# sevenSeg2_atmega_1A_noGND.net
KiCad netlist of a schematic drawn in EAGLE
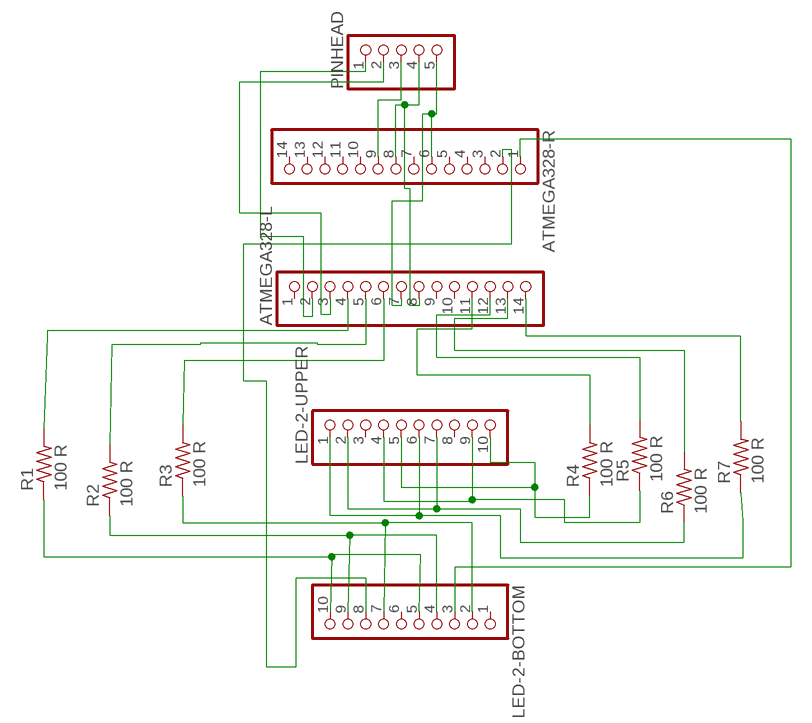
[diagram p0: schematic, sheet 1]

(export (version "E")
  (design (tool "Eeschema 10.0.6"))
  (components
    (comp (ref "ATMEGA328-L")
      (value "PINHD-1X14")
      (footprint "eagle-import:1X14")
      (libsource (lib "eagle-import") (part "PINHD-1X14"))
    )
    (comp (ref "ATMEGA328-R")
      (value "PINHD-1X14")
      (footprint "eagle-import:1X14")
      (libsource (lib "eagle-import") (part "PINHD-1X14"))
    )
    (comp (ref "LED-2-BOTTOM")
      (value "PINHD-1X10")
      (footprint "eagle-import:1X10")
      (libsource (lib "eagle-import") (part "PINHD-1X10"))
    )
    (comp (ref "LED-2-UPPER")
      (value "PINHD-1X10")
      (footprint "eagle-import:1X10")
      (libsource (lib "eagle-import") (part "PINHD-1X10"))
    )
    (comp (ref "PINHEAD")
      (value "PINHD-1X5")
      (footprint "eagle-import:1X05")
      (libsource (lib "eagle-import") (part "PINHD-1X5"))
    )
    (comp (ref "R1")
      (value "100 R")
      (footprint "eagle-import:0204_7")
      (libsource (lib "eagle-import") (part "R-US_0204/7"))
    )
    (comp (ref "R2")
      (value "100 R")
      (footprint "eagle-import:0204_7")
      (libsource (lib "eagle-import") (part "R-US_0204/7"))
    )
    (comp (ref "R3")
      (value "100 R")
      (footprint "eagle-import:0204_7")
      (libsource (lib "eagle-import") (part "R-US_0204/7"))
    )
    (comp (ref "R4")
      (value "100 R")
      (footprint "eagle-import:0204_7")
      (libsource (lib "eagle-import") (part "R-US_0204/7"))
    )
    (comp (ref "R5")
      (value "100 R")
      (footprint "eagle-import:0204_7")
      (libsource (lib "eagle-import") (part "R-US_0204/7"))
    )
    (comp (ref "R6")
      (value "100 R")
      (footprint "eagle-import:0204_7")
      (libsource (lib "eagle-import") (part "R-US_0204/7"))
    )
    (comp (ref "R7")
      (value "100 R")
      (footprint "eagle-import:0204_7")
      (libsource (lib "eagle-import") (part "R-US_0204/7"))
    )
  )
  (nets
    (net (code "1") (name "Net-(ATMEGA328-L-Pad2)") (class "Default")
      (node (ref "ATMEGA328-L") (pin "2") (pinfunction "2_2") (pintype "passive"))
      (node (ref "PINHEAD") (pin "1") (pinfunction "1_1") (pintype "passive"))
    )
    (net (code "2") (name "Net-(ATMEGA328-L-Pad3)") (class "Default")
      (node (ref "ATMEGA328-L") (pin "3") (pinfunction "3_3") (pintype "passive"))
      (node (ref "PINHEAD") (pin "2") (pinfunction "2_2") (pintype "passive"))
    )
    (net (code "3") (name "Net-(ATMEGA328-L-Pad4)") (class "Default")
      (node (ref "ATMEGA328-L") (pin "4") (pinfunction "4_4") (pintype "passive"))
      (node (ref "R1") (pin "2") (pinfunction "2_2") (pintype "passive"))
    )
    (net (code "4") (name "Net-(ATMEGA328-L-Pad5)") (class "Default")
      (node (ref "ATMEGA328-L") (pin "5") (pinfunction "5_5") (pintype "passive"))
      (node (ref "R2") (pin "2") (pinfunction "2_2") (pintype "passive"))
    )
    (net (code "5") (name "Net-(ATMEGA328-L-Pad6)") (class "Default")
      (node (ref "ATMEGA328-L") (pin "6") (pinfunction "6_6") (pintype "passive"))
      (node (ref "R3") (pin "2") (pinfunction "2_2") (pintype "passive"))
    )
    (net (code "6") (name "Net-(ATMEGA328-L-Pad7)") (class "Default")
      (node (ref "ATMEGA328-L") (pin "7") (pinfunction "7_7") (pintype "passive"))
      (node (ref "ATMEGA328-R") (pin "6") (pinfunction "6_6") (pintype "passive"))
      (node (ref "PINHEAD") (pin "5") (pinfunction "5_5") (pintype "passive"))
    )
    (net (code "7") (name "Net-(ATMEGA328-L-Pad8)") (class "Default")
      (node (ref "ATMEGA328-L") (pin "8") (pinfunction "8_8") (pintype "passive"))
      (node (ref "ATMEGA328-R") (pin "8") (pinfunction "8_8") (pintype "passive"))
      (node (ref "PINHEAD") (pin "4") (pinfunction "4_4") (pintype "passive"))
    )
    (net (code "8") (name "Net-(ATMEGA328-L-Pad11)") (class "Default")
      (node (ref "ATMEGA328-L") (pin "11") (pinfunction "11_11") (pintype "passive"))
      (node (ref "R4") (pin "2") (pinfunction "2_2") (pintype "passive"))
    )
    (net (code "9") (name "Net-(ATMEGA328-L-Pad12)") (class "Default")
      (node (ref "ATMEGA328-L") (pin "12") (pinfunction "12_12") (pintype "passive"))
      (node (ref "R5") (pin "2") (pinfunction "2_2") (pintype "passive"))
    )
    (net (code "10") (name "Net-(ATMEGA328-L-Pad13)") (class "Default")
      (node (ref "ATMEGA328-L") (pin "13") (pinfunction "13_13") (pintype "passive"))
      (node (ref "R6") (pin "2") (pinfunction "2_2") (pintype "passive"))
    )
    (net (code "11") (name "Net-(ATMEGA328-L-Pad14)") (class "Default")
      (node (ref "ATMEGA328-L") (pin "14") (pinfunction "14_14") (pintype "passive"))
      (node (ref "R7") (pin "2") (pinfunction "2_2") (pintype "passive"))
    )
    (net (code "12") (name "Net-(ATMEGA328-R-Pad1)") (class "Default")
      (node (ref "ATMEGA328-R") (pin "1") (pinfunction "1_1") (pintype "passive"))
      (node (ref "LED-2-BOTTOM") (pin "3") (pinfunction "3_3") (pintype "passive"))
    )
    (net (code "13") (name "Net-(ATMEGA328-R-Pad2)") (class "Default")
      (node (ref "ATMEGA328-R") (pin "2") (pinfunction "2_2") (pintype "passive"))
      (node (ref "LED-2-BOTTOM") (pin "8") (pinfunction "8_8") (pintype "passive"))
    )
    (net (code "14") (name "Net-(ATMEGA328-R-Pad9)") (class "Default")
      (node (ref "ATMEGA328-R") (pin "9") (pinfunction "9_9") (pintype "passive"))
      (node (ref "PINHEAD") (pin "3") (pinfunction "3_3") (pintype "passive"))
    )
    (net (code "15") (name "Net-(LED-2-BOTTOM-Pad2)") (class "Default")
      (node (ref "LED-2-BOTTOM") (pin "2") (pinfunction "2_2") (pintype "passive"))
      (node (ref "LED-2-BOTTOM") (pin "7") (pinfunction "7_7") (pintype "passive"))
      (node (ref "R3") (pin "1") (pinfunction "1_1") (pintype "passive"))
    )
    (net (code "16") (name "Net-(LED-2-BOTTOM-Pad4)") (class "Default")
      (node (ref "LED-2-BOTTOM") (pin "4") (pinfunction "4_4") (pintype "passive"))
      (node (ref "LED-2-BOTTOM") (pin "9") (pinfunction "9_9") (pintype "passive"))
      (node (ref "R2") (pin "1") (pinfunction "1_1") (pintype "passive"))
    )
    (net (code "17") (name "Net-(LED-2-BOTTOM-Pad10)") (class "Default")
      (node (ref "LED-2-BOTTOM") (pin "10") (pinfunction "10_10") (pintype "passive"))
      (node (ref "LED-2-BOTTOM") (pin "5") (pinfunction "5_5") (pintype "passive"))
      (node (ref "R1") (pin "1") (pinfunction "1_1") (pintype "passive"))
    )
    (net (code "18") (name "Net-(LED-2-UPPER-Pad1)") (class "Default")
      (node (ref "LED-2-UPPER") (pin "1") (pinfunction "1_1") (pintype "passive"))
      (node (ref "LED-2-UPPER") (pin "6") (pinfunction "6_6") (pintype "passive"))
      (node (ref "R7") (pin "1") (pinfunction "1_1") (pintype "passive"))
    )
    (net (code "19") (name "Net-(LED-2-UPPER-Pad2)") (class "Default")
      (node (ref "LED-2-UPPER") (pin "2") (pinfunction "2_2") (pintype "passive"))
      (node (ref "LED-2-UPPER") (pin "7") (pinfunction "7_7") (pintype "passive"))
      (node (ref "R6") (pin "1") (pinfunction "1_1") (pintype "passive"))
    )
    (net (code "20") (name "Net-(LED-2-UPPER-Pad4)") (class "Default")
      (node (ref "LED-2-UPPER") (pin "4") (pinfunction "4_4") (pintype "passive"))
      (node (ref "LED-2-UPPER") (pin "9") (pinfunction "9_9") (pintype "passive"))
      (node (ref "R5") (pin "1") (pinfunction "1_1") (pintype "passive"))
    )
    (net (code "21") (name "Net-(LED-2-UPPER-Pad10)") (class "Default")
      (node (ref "LED-2-UPPER") (pin "10") (pinfunction "10_10") (pintype "passive"))
      (node (ref "LED-2-UPPER") (pin "5") (pinfunction "5_5") (pintype "passive"))
      (node (ref "R4") (pin "1") (pinfunction "1_1") (pintype "passive"))
    )
    (net (code "22") (name "unconnected-(ATMEGA328-L-Pad1)") (class "Default")
      (node (ref "ATMEGA328-L") (pin "1") (pinfunction "1_1") (pintype "passive"))
    )
    (net (code "23") (name "unconnected-(ATMEGA328-L-Pad9)") (class "Default")
      (node (ref "ATMEGA328-L") (pin "9") (pinfunction "9_9") (pintype "passive"))
    )
    (net (code "24") (name "unconnected-(ATMEGA328-L-Pad10)") (class "Default")
      (node (ref "ATMEGA328-L") (pin "10") (pinfunction "10_10") (pintype "passive"))
    )
    (net (code "25") (name "unconnected-(ATMEGA328-R-Pad3)") (class "Default")
      (node (ref "ATMEGA328-R") (pin "3") (pinfunction "3_3") (pintype "passive"))
    )
    (net (code "26") (name "unconnected-(ATMEGA328-R-Pad4)") (class "Default")
      (node (ref "ATMEGA328-R") (pin "4") (pinfunction "4_4") (pintype "passive"))
    )
    (net (code "27") (name "unconnected-(ATMEGA328-R-Pad5)") (class "Default")
      (node (ref "ATMEGA328-R") (pin "5") (pinfunction "5_5") (pintype "passive"))
    )
    (net (code "28") (name "unconnected-(ATMEGA328-R-Pad7)") (class "Default")
      (node (ref "ATMEGA328-R") (pin "7") (pinfunction "7_7") (pintype "passive"))
    )
    (net (code "29") (name "unconnected-(ATMEGA328-R-Pad10)") (class "Default")
      (node (ref "ATMEGA328-R") (pin "10") (pinfunction "10_10") (pintype "passive"))
    )
    (net (code "30") (name "unconnected-(ATMEGA328-R-Pad11)") (class "Default")
      (node (ref "ATMEGA328-R") (pin "11") (pinfunction "11_11") (pintype "passive"))
    )
    (net (code "31") (name "unconnected-(ATMEGA328-R-Pad12)") (class "Default")
      (node (ref "ATMEGA328-R") (pin "12") (pinfunction "12_12") (pintype "passive"))
    )
    (net (code "32") (name "unconnected-(ATMEGA328-R-Pad13)") (class "Default")
      (node (ref "ATMEGA328-R") (pin "13") (pinfunction "13_13") (pintype "passive"))
    )
    (net (code "33") (name "unconnected-(ATMEGA328-R-Pad14)") (class "Default")
      (node (ref "ATMEGA328-R") (pin "14") (pinfunction "14_14") (pintype "passive"))
    )
    (net (code "34") (name "unconnected-(LED-2-BOTTOM-Pad1)") (class "Default")
      (node (ref "LED-2-BOTTOM") (pin "1") (pinfunction "1_1") (pintype "passive"))
    )
    (net (code "35") (name "unconnected-(LED-2-BOTTOM-Pad6)") (class "Default")
      (node (ref "LED-2-BOTTOM") (pin "6") (pinfunction "6_6") (pintype "passive"))
    )
    (net (code "36") (name "unconnected-(LED-2-UPPER-Pad3)") (class "Default")
      (node (ref "LED-2-UPPER") (pin "3") (pinfunction "3_3") (pintype "passive"))
    )
    (net (code "37") (name "unconnected-(LED-2-UPPER-Pad8)") (class "Default")
      (node (ref "LED-2-UPPER") (pin "8") (pinfunction "8_8") (pintype "passive"))
    )
  )
)
